# Sht2-Regulators.net
KiCad netlist of a schematic drawn in Altium Designer
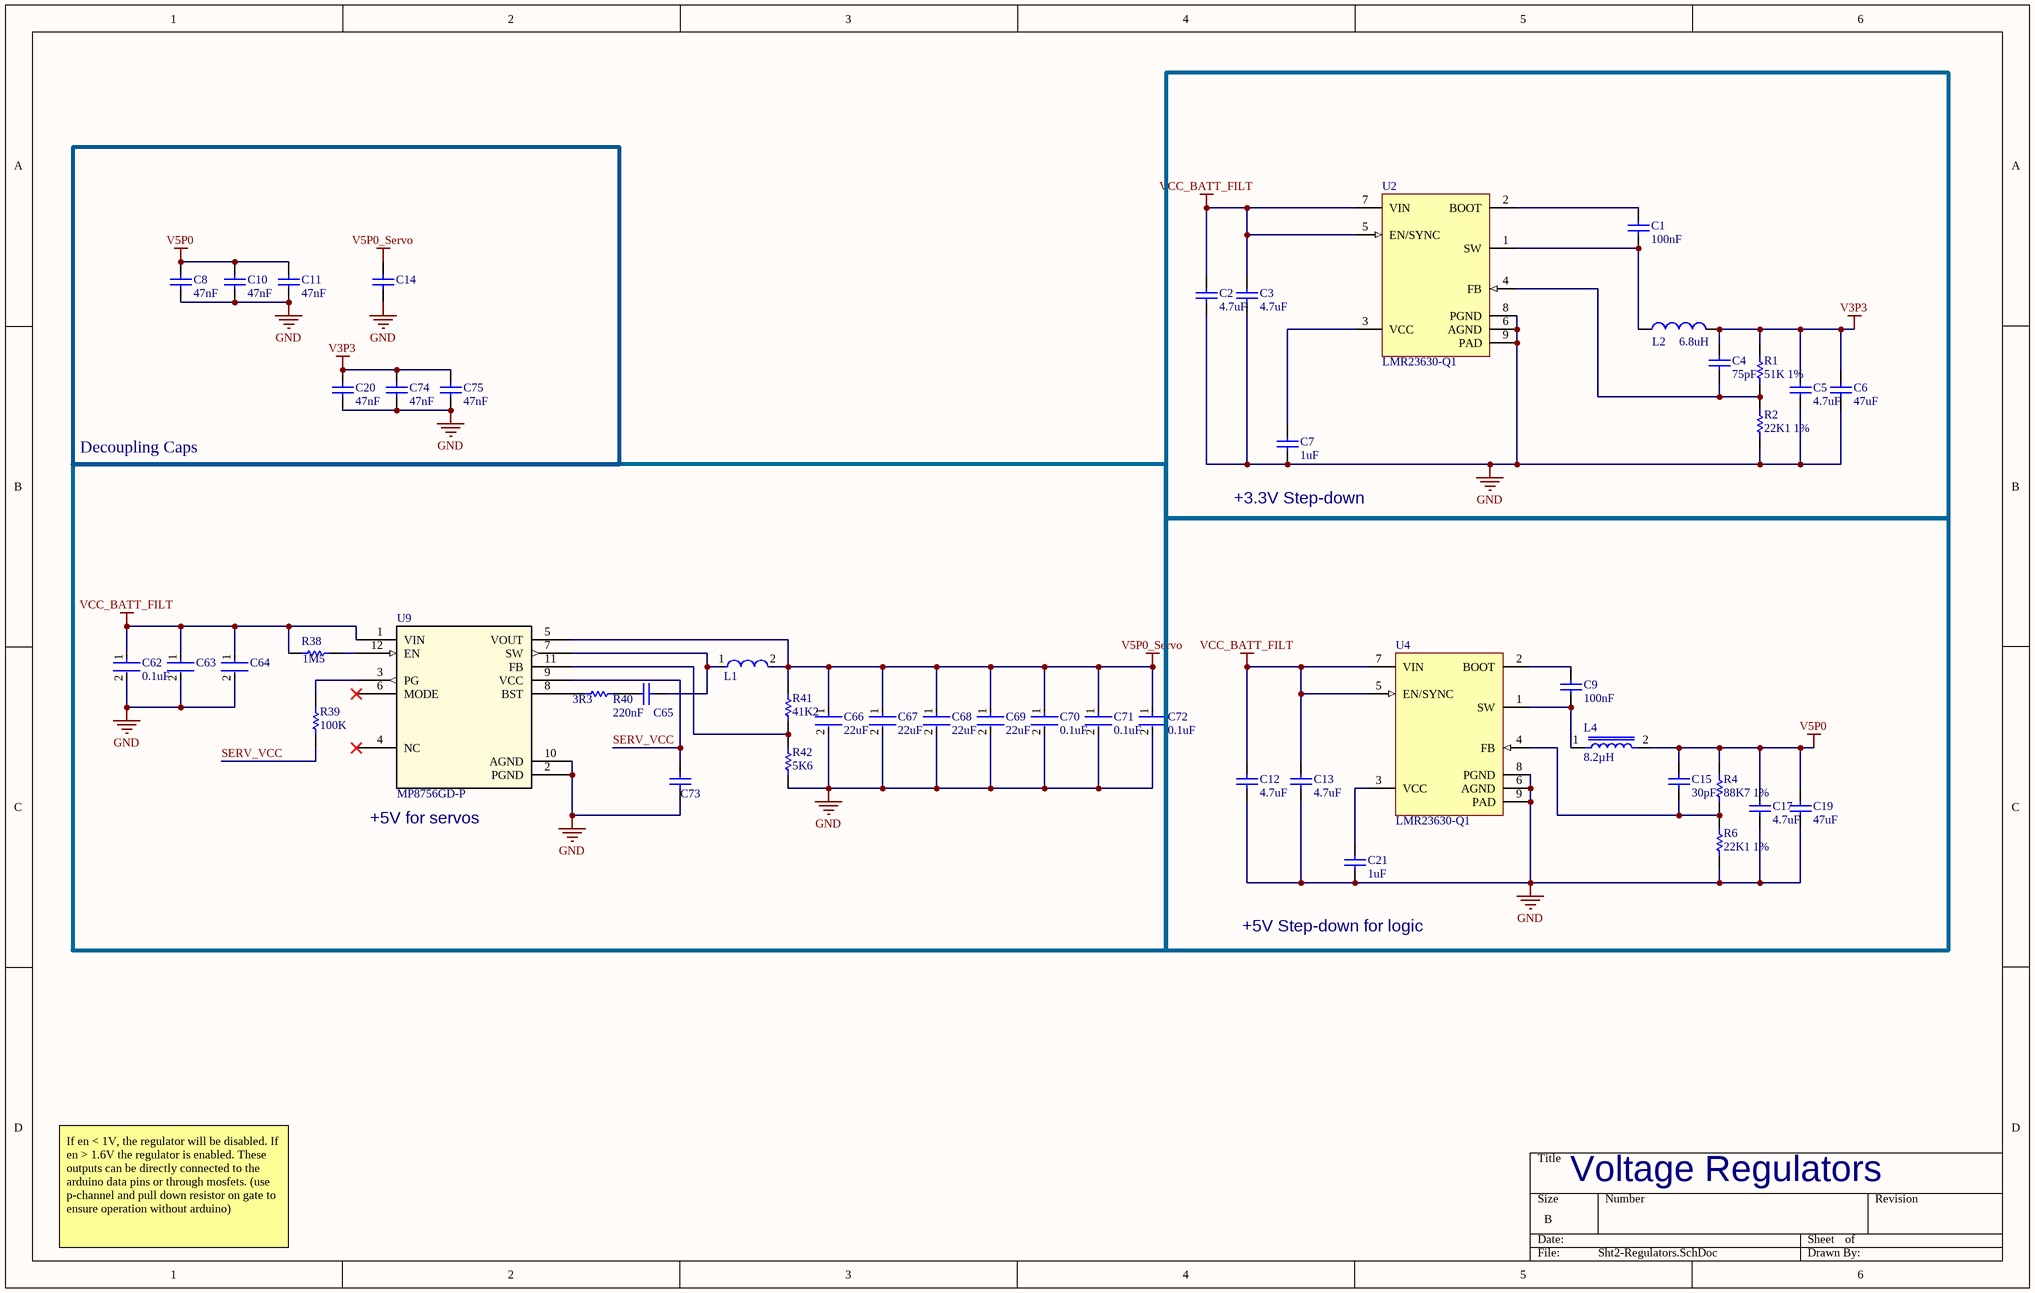
[diagram p0: Sht2-Regulators.SchDoc]

(export (version "E")
  (design (tool "Eeschema 10.0.6"))
  (components
    (comp (ref "C1")
      (value "100nF")
      (footprint "CAPC0603(1608)100_L")
      (description "CAP 100nF 100V ±10% 0603 (1608 Metric) Thickness 1mm SMD")
      (fields (field (name "TOLERANCE") "Â±10%"))
      (libsource (lib "TAUV-Lib") (part "100nF 0603"))
    )
    (comp (ref "C2")
      (value "4.7uF")
      (footprint "CAPC1206(3216)190_L")
      (description "CAP 4.7uF 35V ±10% 1206 (3216 Metric) Thickness 1.9mm SMD")
      (fields (field (name "TOLERANCE") "Â±10%"))
      (libsource (lib "TAUV-Lib") (part "4.7uF 1206"))
    )
    (comp (ref "C3")
      (value "4.7uF")
      (footprint "CAPC1206(3216)190_L")
      (description "CAP 4.7uF 35V ±10% 1206 (3216 Metric) Thickness 1.9mm SMD")
      (fields (field (name "TOLERANCE") "Â±10%"))
      (libsource (lib "TAUV-Lib") (part "4.7uF 1206"))
    )
    (comp (ref "C4")
      (value "75pF")
      (footprint "CAPC0603(1608)100_L")
      (description "CAP 75pF 25V ±1% 0603 (1608 Metric) Thickness 1mm SMD")
      (fields (field (name "TOLERANCE") "Â±1%"))
      (libsource (lib "TAUV-Lib") (part "75pF 0603"))
    )
    (comp (ref "C5")
      (value "4.7uF")
      (footprint "CAPC1206(3216)190_L")
      (description "CAP 4.7uF 35V ±10% 1206 (3216 Metric) Thickness 1.9mm SMD")
      (fields (field (name "TOLERANCE") "Â±10%"))
      (libsource (lib "TAUV-Lib") (part "4.7uF 1206"))
    )
    (comp (ref "C6")
      (value "47uF")
      (footprint "CAPC1206(3216)190_L")
      (description "CAP 47uF 16V ±20% 1206 (3216 Metric) Thickness 1.9mm SMD")
      (fields (field (name "TOLERANCE") "Â±20%"))
      (libsource (lib "TAUV-Lib") (part "47uF 1206"))
    )
    (comp (ref "C7")
      (value "1uF")
      (footprint "CAPC0603(1608)100_L")
      (description "CAP 1uF 25V ±10% 0603 (1608 Metric) Thickness 1mm SMD")
      (fields (field (name "TOLERANCE") "Â±10%"))
      (libsource (lib "TAUV-Lib") (part "1uF 0603"))
    )
    (comp (ref "C8")
      (value "47nF")
      (footprint "CAPC1608X90X35LL10T15")
      (description "47nF 0603")
      (fields (field (name "MANUFACTURER") "Murata") (field (name "PART NUMBER") "GRM188R71E473KA01D"))
      (libsource (lib "TAUV-Lib") (part "47nF 0603"))
    )
    (comp (ref "C9")
      (value "100nF")
      (footprint "CAPC0603(1608)100_L")
      (description "CAP 100nF 100V ±10% 0603 (1608 Metric) Thickness 1mm SMD")
      (fields (field (name "TOLERANCE") "Â±10%"))
      (libsource (lib "TAUV-Lib") (part "100nF 0603"))
    )
    (comp (ref "C10")
      (value "47nF")
      (footprint "CAPC1608X90X35LL10T15")
      (description "47nF 0603")
      (fields (field (name "MANUFACTURER") "Murata") (field (name "PART NUMBER") "GRM188R71E473KA01D"))
      (libsource (lib "TAUV-Lib") (part "47nF 0603"))
    )
    (comp (ref "C11")
      (value "47nF")
      (footprint "CAPC1608X90X35LL10T15")
      (description "47nF 0603")
      (fields (field (name "MANUFACTURER") "Murata") (field (name "PART NUMBER") "GRM188R71E473KA01D"))
      (libsource (lib "TAUV-Lib") (part "47nF 0603"))
    )
    (comp (ref "C12")
      (value "4.7uF")
      (footprint "CAPC1206(3216)190_L")
      (description "CAP 4.7uF 35V ±10% 1206 (3216 Metric) Thickness 1.9mm SMD")
      (fields (field (name "TOLERANCE") "Â±10%"))
      (libsource (lib "TAUV-Lib") (part "4.7uF 1206"))
    )
    (comp (ref "C13")
      (value "4.7uF")
      (footprint "CAPC1206(3216)190_L")
      (description "CAP 4.7uF 35V ±10% 1206 (3216 Metric) Thickness 1.9mm SMD")
      (fields (field (name "TOLERANCE") "Â±10%"))
      (libsource (lib "TAUV-Lib") (part "4.7uF 1206"))
    )
    (comp (ref "C14")
      (value "~")
      (footprint "CAPC1608X90X35LL10T15")
      (description "47nF 0603")
      (fields (field (name "MANUFACTURER") "Murata") (field (name "PART NUMBER") "GRM188R71E473KA01D"))
      (libsource (lib "TAUV-Lib") (part "47nF 0603"))
    )
    (comp (ref "C15")
      (value "30pF")
      (footprint "0603")
      (description "CAP 30pF 50V ±10% 0603 (1608 Metric) Thickness 1mm SMD")
      (fields (field (name "TOLERANCE") "Â±10%"))
      (libsource (lib "TAUV-Lib") (part "30pF 0603"))
    )
    (comp (ref "C17")
      (value "4.7uF")
      (footprint "CAPC1206(3216)190_L")
      (description "CAP 4.7uF 35V ±10% 1206 (3216 Metric) Thickness 1.9mm SMD")
      (fields (field (name "TOLERANCE") "Â±10%"))
      (libsource (lib "TAUV-Lib") (part "4.7uF 1206"))
    )
    (comp (ref "C19")
      (value "47uF")
      (footprint "CAPC1206(3216)190_L")
      (description "CAP 47uF 16V ±20% 1206 (3216 Metric) Thickness 1.9mm SMD")
      (fields (field (name "TOLERANCE") "Â±20%"))
      (libsource (lib "TAUV-Lib") (part "47uF 1206"))
    )
    (comp (ref "C20")
      (value "47nF")
      (footprint "CAPC1608X90X35LL10T15")
      (description "47nF 0603")
      (fields (field (name "MANUFACTURER") "Murata") (field (name "PART NUMBER") "GRM188R71E473KA01D"))
      (libsource (lib "TAUV-Lib") (part "47nF 0603"))
    )
    (comp (ref "C21")
      (value "1uF")
      (footprint "CAPC0603(1608)100_L")
      (description "CAP 1uF 25V ±10% 0603 (1608 Metric) Thickness 1mm SMD")
      (fields (field (name "TOLERANCE") "Â±10%"))
      (libsource (lib "TAUV-Lib") (part "1uF 0603"))
    )
    (comp (ref "C62")
      (value "0.1uF")
      (footprint "FP-CC0603-DA-MFG")
      (description "CC0603KRX7R9BB104-CAP CER 0.1UF 50V X7R 0603")
      (fields (field (name "MANUFACTURER") "YAGEO") (field (name "VOLTAGE") "50 V"))
      (libsource (lib "TAUV-Lib") (part "0.1uF 0603"))
    )
    (comp (ref "C63")
      (value "~")
      (footprint "0603")
      (description "Cap Ceramic 22uF 10V X5R ±20% Pad SMD 0603 +85°C T/R")
      (fields (field (name "TOLERANCE") "20%"))
      (libsource (lib "TAUV-Lib") (part "22uF 0603"))
    )
    (comp (ref "C64")
      (value "~")
      (footprint "0603")
      (description "Cap Ceramic 22uF 10V X5R ±20% Pad SMD 0603 +85°C T/R")
      (fields (field (name "TOLERANCE") "20%"))
      (libsource (lib "TAUV-Lib") (part "22uF 0603"))
    )
    (comp (ref "C65")
      (value "220nF")
      (footprint "CAPC1608X87X35NL15T15")
      (description "C0603C224K8NACTU-220nF 0603")
      (fields (field (name "PART NUMBER") "C0603C224K8NACTU") (field (name "MANUFACTURER") "Kemet"))
      (libsource (lib "TAUV-Lib") (part "220nF 0603"))
    )
    (comp (ref "C66")
      (value "22uF")
      (footprint "0603")
      (description "Cap Ceramic 22uF 10V X5R ±20% Pad SMD 0603 +85°C T/R")
      (fields (field (name "TOLERANCE") "20%"))
      (libsource (lib "TAUV-Lib") (part "22uF 0603"))
    )
    (comp (ref "C67")
      (value "22uF")
      (footprint "0603")
      (description "Cap Ceramic 22uF 10V X5R ±20% Pad SMD 0603 +85°C T/R")
      (fields (field (name "TOLERANCE") "20%"))
      (libsource (lib "TAUV-Lib") (part "22uF 0603"))
    )
    (comp (ref "C68")
      (value "22uF")
      (footprint "0603")
      (description "Cap Ceramic 22uF 10V X5R ±20% Pad SMD 0603 +85°C T/R")
      (fields (field (name "TOLERANCE") "20%"))
      (libsource (lib "TAUV-Lib") (part "22uF 0603"))
    )
    (comp (ref "C69")
      (value "22uF")
      (footprint "0603")
      (description "Cap Ceramic 22uF 10V X5R ±20% Pad SMD 0603 +85°C T/R")
      (fields (field (name "TOLERANCE") "20%"))
      (libsource (lib "TAUV-Lib") (part "22uF 0603"))
    )
    (comp (ref "C70")
      (value "0.1uF")
      (footprint "FP-CC0603-DA-MFG")
      (description "CC0603KRX7R9BB104-CAP CER 0.1UF 50V X7R 0603")
      (fields (field (name "MANUFACTURER") "YAGEO") (field (name "VOLTAGE") "50 V"))
      (libsource (lib "TAUV-Lib") (part "0.1uF 0603"))
    )
    (comp (ref "C71")
      (value "0.1uF")
      (footprint "FP-CC0603-DA-MFG")
      (description "CC0603KRX7R9BB104-CAP CER 0.1UF 50V X7R 0603")
      (fields (field (name "MANUFACTURER") "YAGEO") (field (name "VOLTAGE") "50 V"))
      (libsource (lib "TAUV-Lib") (part "0.1uF 0603"))
    )
    (comp (ref "C72")
      (value "0.1uF")
      (footprint "FP-CC0603-DA-MFG")
      (description "CC0603KRX7R9BB104-CAP CER 0.1UF 50V X7R 0603")
      (fields (field (name "MANUFACTURER") "YAGEO") (field (name "VOLTAGE") "50 V"))
      (libsource (lib "TAUV-Lib") (part "0.1uF 0603"))
    )
    (comp (ref "C73")
      (value "~")
      (footprint "0603")
      (description "CAP 1uF 25V ±10% 0603 (1608 Metric) Thickness 1mm SMD")
      (fields (field (name "TOLERANCE") "Â±10%"))
      (libsource (lib "TAUV-Lib") (part "1uF 0603"))
    )
    (comp (ref "C74")
      (value "47nF")
      (footprint "CAPC1608X90X35LL10T15")
      (description "47nF 0603")
      (fields (field (name "MANUFACTURER") "Murata") (field (name "PART NUMBER") "GRM188R71E473KA01D"))
      (libsource (lib "TAUV-Lib") (part "47nF 0603"))
    )
    (comp (ref "C75")
      (value "47nF")
      (footprint "CAPC1608X90X35LL10T15")
      (description "47nF 0603")
      (fields (field (name "MANUFACTURER") "Murata") (field (name "PART NUMBER") "GRM188R71E473KA01D"))
      (libsource (lib "TAUV-Lib") (part "47nF 0603"))
    )
    (comp (ref "L1")
      (value "~")
      (footprint "FP-IHLP-2525CZ-FP_2_413x3-MFG")
      (description "Commercial Inductors, High Saturation Series 1.5uH 9A 15mΩ 20%")
      (fields (field (name "TOLERANCE") "20%"))
      (libsource (lib "TAUV-Lib") (part "1.5uH 9A inductor"))
    )
    (comp (ref "L2")
      (value "6.8uH")
      (footprint "BOURNS SRP5030T")
      (fields
        (field (name "MANUFACTURER") "Bourns Inc.")
        (field (name "MANUFACTURER PART NUMBER") "SRP5030TA-6R8M")
        (field (name "TOLERANCE") "±20%")
      )
      (libsource (lib "TAUV-Lib") (part "SRP5030TA"))
    )
    (comp (ref "L4")
      (value "8.2µH")
      (footprint "TAUV-Lib:IND_SRP6540-8R2M")
      (description "8.2µH Shielded Wirewound Inductor 4.5A 50.5mOhm Max Nonstandard")
      (fields (field (name "MP") "SRP6540-8R2M") (field (name "DIGI-KEY_PART_NUMBER") "SRP6540-8R2MCT-ND"))
      (libsource (lib "TAUV-Lib") (part "SRP6540-8R2M"))
    )
    (comp (ref "R1")
      (value "51K 1%")
      (footprint "RESC0603(1608)_L")
      (description "51K 0.1W 1% 0603 (1608 Metric)  SMD")
      (fields (field (name "TOLERANCE") "1 %") (field (name "POWER") "0.1 W"))
      (libsource (lib "TAUV-Lib") (part "51K 0603"))
    )
    (comp (ref "R2")
      (value "22K1 1%")
      (footprint "RESC0603(1608)_L")
      (description "22K1 0.1W 1% 0603 (1608 Metric)  SMD")
      (fields (field (name "TOLERANCE") "1 %") (field (name "POWER") "0.1 W"))
      (libsource (lib "TAUV-Lib") (part "22K1 0603"))
    )
    (comp (ref "R4")
      (value "88K7 1%")
      (footprint "RESC0603(1608)_L")
      (description "88K7 0.1W 1% 0603 (1608 Metric)  SMD")
      (fields (field (name "TOLERANCE") "1 %") (field (name "POWER") "0.1 W"))
      (libsource (lib "TAUV-Lib") (part "88K7 0603"))
    )
    (comp (ref "R6")
      (value "22K1 1%")
      (footprint "RESC0603(1608)_L")
      (description "22K1 0.1W 1% 0603 (1608 Metric)  SMD")
      (fields (field (name "TOLERANCE") "1 %") (field (name "POWER") "0.1 W"))
      (libsource (lib "TAUV-Lib") (part "22K1 0603"))
    )
    (comp (ref "R38")
      (value "1M5")
      (footprint "RESC1609X50X30NL10T20")
      (description "CRCW06031M50FKEA-1M5 0603")
      (fields (field (name "MANUFACTURER") "Vishay Dale") (field (name "PART NUMBER") "CRCW06031M50FKEA"))
      (libsource (lib "TAUV-Lib") (part "1M5 0603"))
    )
    (comp (ref "R39")
      (value "100K")
      (footprint "0603")
      (description "ERJ-3EKF1003V-100k 0603")
      (fields (field (name "PART NUMBER") "ERJ-3EKF1003V") (field (name "MANUFACTURER") "Panasonic"))
      (libsource (lib "TAUV-Lib") (part "100K 0603"))
    )
    (comp (ref "R40")
      (value "3R3")
      (footprint "RESC1608X55X30NL15T15")
      (description "ERJ-3RQF3R3V- 3R3 0603")
      (fields (field (name "PART NUMBER") "ERJ-3RQF3R3V") (field (name "MANUFACTURER") "Panasonic"))
      (libsource (lib "TAUV-Lib") (part "3R3 0603"))
    )
    (comp (ref "R41")
      (value "41K2")
      (footprint "RESC1608X55X30LL20T20")
      (description "ERA3AEB4122V-41k2 0603")
      (fields (field (name "MANUFACTURER") "Panasonic") (field (name "PART NUMBER") "ERA3AEB4122V"))
      (libsource (lib "TAUV-Lib") (part "41K2 0603"))
    )
    (comp (ref "R42")
      (value "5K6")
      (footprint "RESC1609X55X30LL15T15")
      (description "Chip Resistor, 5.6 KOhm, +/- 1%, 0.1 W, -55 to 155 degC, 0603 (1608 Metric), RoHS, Tape and Reel")
      (libsource (lib "TAUV-Lib") (part "5K6 0603"))
    )
    (comp (ref "U2")
      (value "LMR23630-Q1")
      (footprint "DDA0008E_N")
      (fields
        (field (name "MANUFACTURER") "Texas Instruments")
        (field (name "MANUFACTURER PART NUMBER") "LMR23630AFQDDARQ1")
      )
      (libsource (lib "TAUV-Lib") (part "LMR23630-Q1"))
    )
    (comp (ref "U4")
      (value "LMR23630-Q1")
      (footprint "DDA0008E_N")
      (fields
        (field (name "MANUFACTURER") "Texas Instruments")
        (field (name "MANUFACTURER PART NUMBER") "LMR23630AFQDDARQ1")
      )
      (libsource (lib "TAUV-Lib") (part "LMR23630-Q1"))
    )
    (comp (ref "U9")
      (value "MP8756GD-P")
      (footprint "QFN-12_MP8756_MNP")
      (description "No Description Available")
      (libsource (lib "TAUV-Lib") (part "MP8756GD-P"))
    )
  )
  (nets
    (net (code "1") (name "/SERV_VCC") (class "Default")
      (node (ref "C73") (pin "2") (pinfunction "2_2") (pintype "passive"))
      (node (ref "R39") (pin "2") (pinfunction "2_2") (pintype "passive"))
      (node (ref "U9") (pin "9") (pinfunction "VCC_9") (pintype "power_in"))
    )
    (net (code "2") (name "GND") (class "Default")
      (node (ref "C10") (pin "2") (pinfunction "2_2") (pintype "passive"))
      (node (ref "C11") (pin "2") (pinfunction "2_2") (pintype "passive"))
      (node (ref "C12") (pin "2") (pinfunction "2_2") (pintype "passive"))
      (node (ref "C13") (pin "2") (pinfunction "2_2") (pintype "passive"))
      (node (ref "C14") (pin "2") (pinfunction "2_2") (pintype "passive"))
      (node (ref "C17") (pin "2") (pinfunction "2_2") (pintype "passive"))
      (node (ref "C19") (pin "2") (pinfunction "2_2") (pintype "passive"))
      (node (ref "C2") (pin "2") (pinfunction "2_2") (pintype "passive"))
      (node (ref "C20") (pin "2") (pinfunction "2_2") (pintype "passive"))
      (node (ref "C21") (pin "2") (pinfunction "2_2") (pintype "passive"))
      (node (ref "C3") (pin "2") (pinfunction "2_2") (pintype "passive"))
      (node (ref "C5") (pin "2") (pinfunction "2_2") (pintype "passive"))
      (node (ref "C6") (pin "2") (pinfunction "2_2") (pintype "passive"))
      (node (ref "C62") (pin "2") (pinfunction "2_2") (pintype "passive"))
      (node (ref "C63") (pin "2") (pinfunction "2_2") (pintype "passive"))
      (node (ref "C64") (pin "2") (pinfunction "2_2") (pintype "passive"))
      (node (ref "C66") (pin "2") (pinfunction "2_2") (pintype "passive"))
      (node (ref "C67") (pin "2") (pinfunction "2_2") (pintype "passive"))
      (node (ref "C68") (pin "2") (pinfunction "2_2") (pintype "passive"))
      (node (ref "C69") (pin "2") (pinfunction "2_2") (pintype "passive"))
      (node (ref "C7") (pin "2") (pinfunction "2_2") (pintype "passive"))
      (node (ref "C70") (pin "2") (pinfunction "2_2") (pintype "passive"))
      (node (ref "C71") (pin "2") (pinfunction "2_2") (pintype "passive"))
      (node (ref "C72") (pin "2") (pinfunction "2_2") (pintype "passive"))
      (node (ref "C73") (pin "1") (pinfunction "1_1") (pintype "passive"))
      (node (ref "C74") (pin "2") (pinfunction "2_2") (pintype "passive"))
      (node (ref "C75") (pin "2") (pinfunction "2_2") (pintype "passive"))
      (node (ref "C8") (pin "2") (pinfunction "2_2") (pintype "passive"))
      (node (ref "R2") (pin "2") (pinfunction "2_2") (pintype "passive"))
      (node (ref "R42") (pin "2") (pinfunction "2_2") (pintype "passive"))
      (node (ref "R6") (pin "2") (pinfunction "2_2") (pintype "passive"))
      (node (ref "U2") (pin "6") (pinfunction "AGND_6") (pintype "passive"))
      (node (ref "U2") (pin "8") (pinfunction "PGND_8") (pintype "passive"))
      (node (ref "U2") (pin "9") (pinfunction "PAD_9") (pintype "passive"))
      (node (ref "U4") (pin "6") (pinfunction "AGND_6") (pintype "passive"))
      (node (ref "U4") (pin "8") (pinfunction "PGND_8") (pintype "passive"))
      (node (ref "U4") (pin "9") (pinfunction "PAD_9") (pintype "passive"))
      (node (ref "U9") (pin "10") (pinfunction "AGND_10") (pintype "power_in"))
      (node (ref "U9") (pin "2") (pinfunction "PGND_2") (pintype "power_in"))
    )
    (net (code "3") (name "Net-(C65-Pad1)") (class "Default")
      (node (ref "C65") (pin "1") (pinfunction "1_1") (pintype "passive"))
      (node (ref "R40") (pin "2") (pinfunction "2_2") (pintype "passive"))
    )
    (net (code "4") (name "Net-(U2-BOOT)") (class "Default")
      (node (ref "C1") (pin "1") (pinfunction "1_1") (pintype "passive"))
      (node (ref "U2") (pin "2") (pinfunction "BOOT_2") (pintype "passive"))
    )
    (net (code "5") (name "Net-(U2-FB)") (class "Default")
      (node (ref "C4") (pin "2") (pinfunction "2_2") (pintype "passive"))
      (node (ref "R1") (pin "2") (pinfunction "2_2") (pintype "passive"))
      (node (ref "R2") (pin "1") (pinfunction "1_1") (pintype "passive"))
      (node (ref "U2") (pin "4") (pinfunction "FB_4") (pintype "input"))
    )
    (net (code "6") (name "Net-(U2-SW)") (class "Default")
      (node (ref "C1") (pin "2") (pinfunction "2_2") (pintype "passive"))
      (node (ref "L2") (pin "1") (pinfunction "1_1") (pintype "passive"))
      (node (ref "U2") (pin "1") (pinfunction "SW_1") (pintype "passive"))
    )
    (net (code "7") (name "Net-(U2-VCC)") (class "Default")
      (node (ref "C7") (pin "1") (pinfunction "1_1") (pintype "passive"))
      (node (ref "U2") (pin "3") (pinfunction "VCC_3") (pintype "passive"))
    )
    (net (code "8") (name "Net-(U4-BOOT)") (class "Default")
      (node (ref "C9") (pin "1") (pinfunction "1_1") (pintype "passive"))
      (node (ref "U4") (pin "2") (pinfunction "BOOT_2") (pintype "passive"))
    )
    (net (code "9") (name "Net-(U4-FB)") (class "Default")
      (node (ref "C15") (pin "2") (pinfunction "2_2") (pintype "passive"))
      (node (ref "R4") (pin "2") (pinfunction "2_2") (pintype "passive"))
      (node (ref "R6") (pin "1") (pinfunction "1_1") (pintype "passive"))
      (node (ref "U4") (pin "4") (pinfunction "FB_4") (pintype "input"))
    )
    (net (code "10") (name "Net-(U4-SW)") (class "Default")
      (node (ref "C9") (pin "2") (pinfunction "2_2") (pintype "passive"))
      (node (ref "L4") (pin "1") (pinfunction "1_1") (pintype "passive"))
      (node (ref "U4") (pin "1") (pinfunction "SW_1") (pintype "passive"))
    )
    (net (code "11") (name "Net-(U4-VCC)") (class "Default")
      (node (ref "C21") (pin "1") (pinfunction "1_1") (pintype "passive"))
      (node (ref "U4") (pin "3") (pinfunction "VCC_3") (pintype "passive"))
    )
    (net (code "12") (name "Net-(U9-BST)") (class "Default")
      (node (ref "R40") (pin "1") (pinfunction "1_1") (pintype "passive"))
      (node (ref "U9") (pin "8") (pinfunction "BST_8") (pintype "power_in"))
    )
    (net (code "13") (name "Net-(U9-EN)") (class "Default")
      (node (ref "R38") (pin "2") (pinfunction "2_2") (pintype "passive"))
      (node (ref "U9") (pin "12") (pinfunction "EN_12") (pintype "input"))
    )
    (net (code "14") (name "Net-(U9-FB)") (class "Default")
      (node (ref "R41") (pin "2") (pinfunction "2_2") (pintype "passive"))
      (node (ref "R42") (pin "1") (pinfunction "1_1") (pintype "passive"))
      (node (ref "U9") (pin "11") (pinfunction "FB_11") (pintype "passive"))
    )
    (net (code "15") (name "Net-(U9-PG)") (class "Default")
      (node (ref "R39") (pin "1") (pinfunction "1_1") (pintype "passive"))
      (node (ref "U9") (pin "3") (pinfunction "PG_3") (pintype "output"))
    )
    (net (code "16") (name "Net-(U9-SW)") (class "Default")
      (node (ref "C65") (pin "2") (pinfunction "2_2") (pintype "passive"))
      (node (ref "L1") (pin "1") (pinfunction "1_1") (pintype "passive"))
      (node (ref "U9") (pin "7") (pinfunction "SW_7") (pintype "output"))
    )
    (net (code "17") (name "V3P3") (class "Default")
      (node (ref "C20") (pin "1") (pinfunction "1_1") (pintype "passive"))
      (node (ref "C4") (pin "1") (pinfunction "1_1") (pintype "passive"))
      (node (ref "C5") (pin "1") (pinfunction "1_1") (pintype "passive"))
      (node (ref "C6") (pin "1") (pinfunction "1_1") (pintype "passive"))
      (node (ref "C74") (pin "1") (pinfunction "1_1") (pintype "passive"))
      (node (ref "C75") (pin "1") (pinfunction "1_1") (pintype "passive"))
      (node (ref "L2") (pin "2") (pinfunction "2_2") (pintype "passive"))
      (node (ref "R1") (pin "1") (pinfunction "1_1") (pintype "passive"))
    )
    (net (code "18") (name "V5P0") (class "Default")
      (node (ref "C10") (pin "1") (pinfunction "1_1") (pintype "passive"))
      (node (ref "C11") (pin "1") (pinfunction "1_1") (pintype "passive"))
      (node (ref "C15") (pin "1") (pinfunction "1_1") (pintype "passive"))
      (node (ref "C17") (pin "1") (pinfunction "1_1") (pintype "passive"))
      (node (ref "C19") (pin "1") (pinfunction "1_1") (pintype "passive"))
      (node (ref "C8") (pin "1") (pinfunction "1_1") (pintype "passive"))
      (node (ref "L4") (pin "2") (pinfunction "2_2") (pintype "passive"))
      (node (ref "R4") (pin "1") (pinfunction "1_1") (pintype "passive"))
    )
    (net (code "19") (name "V5P0_Servo") (class "Default")
      (node (ref "C14") (pin "1") (pinfunction "1_1") (pintype "passive"))
      (node (ref "C66") (pin "1") (pinfunction "1_1") (pintype "passive"))
      (node (ref "C67") (pin "1") (pinfunction "1_1") (pintype "passive"))
      (node (ref "C68") (pin "1") (pinfunction "1_1") (pintype "passive"))
      (node (ref "C69") (pin "1") (pinfunction "1_1") (pintype "passive"))
      (node (ref "C70") (pin "1") (pinfunction "1_1") (pintype "passive"))
      (node (ref "C71") (pin "1") (pinfunction "1_1") (pintype "passive"))
      (node (ref "C72") (pin "1") (pinfunction "1_1") (pintype "passive"))
      (node (ref "L1") (pin "2") (pinfunction "2_2") (pintype "passive"))
      (node (ref "R41") (pin "1") (pinfunction "1_1") (pintype "passive"))
      (node (ref "U9") (pin "5") (pinfunction "VOUT_5") (pintype "power_in"))
    )
    (net (code "20") (name "VCC_BATT_FILT") (class "Default")
      (node (ref "C12") (pin "1") (pinfunction "1_1") (pintype "passive"))
      (node (ref "C13") (pin "1") (pinfunction "1_1") (pintype "passive"))
      (node (ref "C2") (pin "1") (pinfunction "1_1") (pintype "passive"))
      (node (ref "C3") (pin "1") (pinfunction "1_1") (pintype "passive"))
      (node (ref "C62") (pin "1") (pinfunction "1_1") (pintype "passive"))
      (node (ref "C63") (pin "1") (pinfunction "1_1") (pintype "passive"))
      (node (ref "C64") (pin "1") (pinfunction "1_1") (pintype "passive"))
      (node (ref "R38") (pin "1") (pinfunction "1_1") (pintype "passive"))
      (node (ref "U2") (pin "5") (pinfunction "EN/SYNC_5") (pintype "input"))
      (node (ref "U2") (pin "7") (pinfunction "VIN_7") (pintype "passive"))
      (node (ref "U4") (pin "5") (pinfunction "EN/SYNC_5") (pintype "input"))
      (node (ref "U4") (pin "7") (pinfunction "VIN_7") (pintype "passive"))
      (node (ref "U9") (pin "1") (pinfunction "VIN_1") (pintype "power_in"))
    )
    (net (code "21") (name "unconnected-(U9-MODE-Pad6)") (class "Default")
      (node (ref "U9") (pin "6") (pinfunction "MODE_6") (pintype "passive+no_connect"))
    )
    (net (code "22") (name "unconnected-(U9-NC-Pad4)") (class "Default")
      (node (ref "U9") (pin "4") (pinfunction "NC_4") (pintype "passive+no_connect"))
    )
  )
)
